# LCDTFT_FPC40P_DBI16B_3_2INCH_RTP.net
KiCad netlist of a schematic drawn in Altium Designer
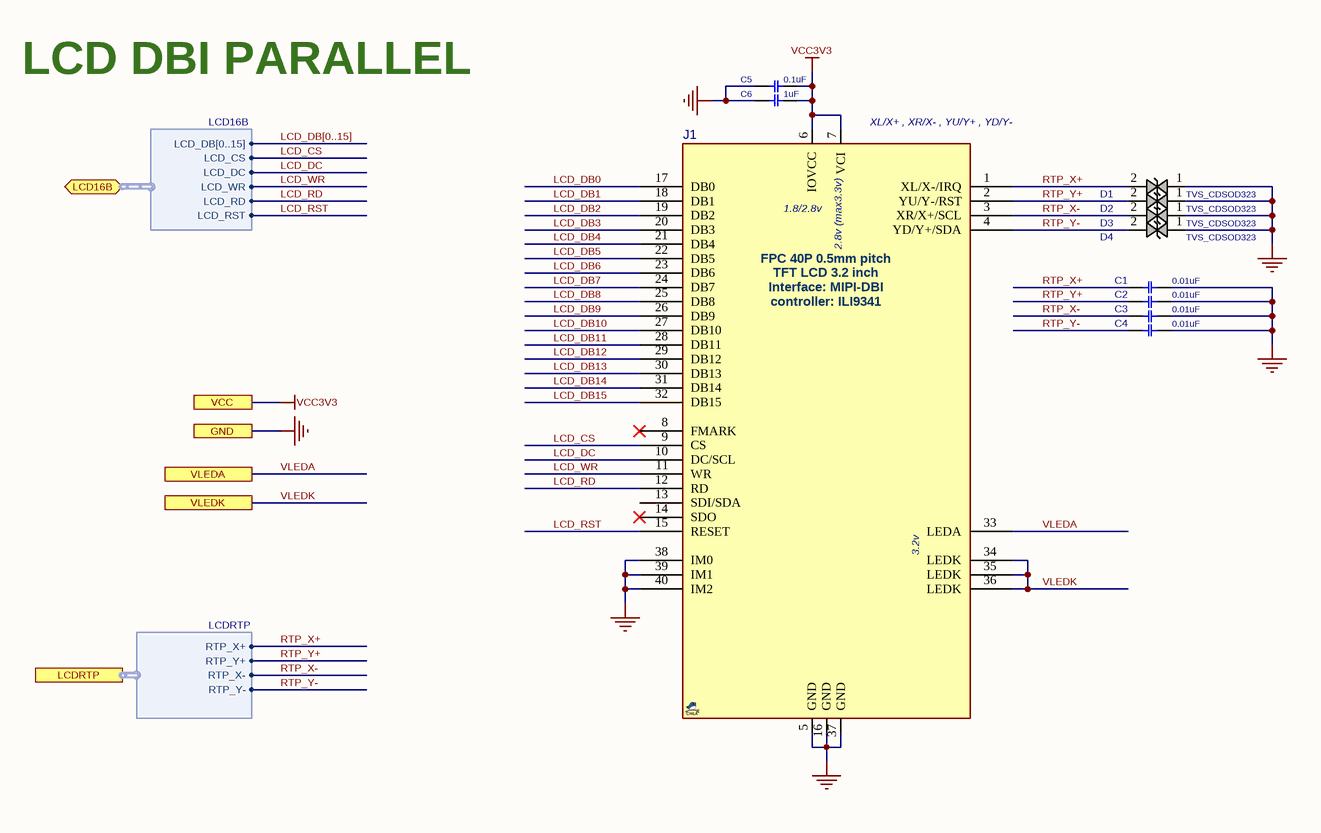
[diagram p0: LCDTFT_FPC40P_DBI16B_3.2INCH_RTP.SchDoc]

(export (version "E")
  (design (tool "Eeschema 10.0.6"))
  (components
    (comp (ref "C1")
      (value "0.01uF")
      (footprint "C0402")
      (description "CAP, MLCC")
      (libsource (lib "passive_smd") (part "CAP_SMD_MLCC"))
    )
    (comp (ref "C2")
      (value "0.01uF")
      (footprint "C0402")
      (description "CAP, MLCC")
      (libsource (lib "passive_smd") (part "CAP_SMD_MLCC"))
    )
    (comp (ref "C3")
      (value "0.01uF")
      (footprint "C0402")
      (description "CAP, MLCC")
      (libsource (lib "passive_smd") (part "CAP_SMD_MLCC"))
    )
    (comp (ref "C4")
      (value "0.01uF")
      (footprint "C0402")
      (description "CAP, MLCC")
      (libsource (lib "passive_smd") (part "CAP_SMD_MLCC"))
    )
    (comp (ref "C5")
      (value "0.1uF")
      (footprint "C0402")
      (description "CAP, MLCC")
      (fields (field (name "MANF_P#") "GRM155R71H104KE14D") (field (name "MANF") "Murata"))
      (libsource (lib "passive_smd") (part "CAP_SMD_MLCC"))
    )
    (comp (ref "C6")
      (value "1uF")
      (footprint "C0402")
      (description "CAP, MLCC")
      (libsource (lib "passive_smd") (part "CAP_SMD_MLCC"))
    )
    (comp (ref "D1")
      (value "TVS_CDSOD323")
      (footprint "D0805")
      (description "TVS, ESD PROTECT, Bidirectional")
      (fields (field (name "MANF_P#") "CDSOD323-T12C") (field (name "MANF") "Bourns"))
      (libsource (lib "protect_tvs_esd_fuse") (part "TVS_CDSOD323"))
    )
    (comp (ref "D2")
      (value "TVS_CDSOD323")
      (footprint "D0805")
      (description "TVS, ESD PROTECT, Bidirectional")
      (fields (field (name "MANF_P#") "CDSOD323-T12C") (field (name "MANF") "Bourns"))
      (libsource (lib "protect_tvs_esd_fuse") (part "TVS_CDSOD323"))
    )
    (comp (ref "D3")
      (value "TVS_CDSOD323")
      (footprint "D0805")
      (description "TVS, ESD PROTECT, Bidirectional")
      (fields (field (name "MANF_P#") "CDSOD323-T12C") (field (name "MANF") "Bourns"))
      (libsource (lib "protect_tvs_esd_fuse") (part "TVS_CDSOD323"))
    )
    (comp (ref "D4")
      (value "TVS_CDSOD323")
      (footprint "D0805")
      (description "TVS, ESD PROTECT, Bidirectional")
      (fields (field (name "MANF_P#") "CDSOD323-T12C") (field (name "MANF") "Bourns"))
      (libsource (lib "protect_tvs_esd_fuse") (part "TVS_CDSOD323"))
    )
    (comp (ref "J1")
      (value "FPC50_40")
      (footprint "FPC50_40T")
      (description "LCD TFT Color, FPC40P, 3.2\" with touch")
      (fields (field (name "MANF") "Hirose") (field (name "MANF_P#") "FH12A-40S-0.5SH"))
      (libsource (lib "lcdtft") (part "LCDTFT_DBI_FPC40P_3.2INCH"))
    )
  )
  (nets
    (net (code "3") (name "/LCD_CS") (class "Default")
      (node (ref "J1") (pin "9") (pinfunction "CS_9") (pintype "passive"))
    )
    (net (code "4") (name "/LCD_DB0") (class "Default")
      (node (ref "J1") (pin "17") (pinfunction "DB0_17") (pintype "passive"))
    )
    (net (code "5") (name "/LCD_DB1") (class "Default")
      (node (ref "J1") (pin "18") (pinfunction "DB1_18") (pintype "passive"))
    )
    (net (code "6") (name "/LCD_DB2") (class "Default")
      (node (ref "J1") (pin "19") (pinfunction "DB2_19") (pintype "passive"))
    )
    (net (code "7") (name "/LCD_DB3") (class "Default")
      (node (ref "J1") (pin "20") (pinfunction "DB3_20") (pintype "passive"))
    )
    (net (code "8") (name "/LCD_DB4") (class "Default")
      (node (ref "J1") (pin "21") (pinfunction "DB4_21") (pintype "passive"))
    )
    (net (code "9") (name "/LCD_DB5") (class "Default")
      (node (ref "J1") (pin "22") (pinfunction "DB5_22") (pintype "passive"))
    )
    (net (code "10") (name "/LCD_DB6") (class "Default")
      (node (ref "J1") (pin "23") (pinfunction "DB6_23") (pintype "passive"))
    )
    (net (code "11") (name "/LCD_DB7") (class "Default")
      (node (ref "J1") (pin "24") (pinfunction "DB7_24") (pintype "passive"))
    )
    (net (code "12") (name "/LCD_DB8") (class "Default")
      (node (ref "J1") (pin "25") (pinfunction "DB8_25") (pintype "passive"))
    )
    (net (code "13") (name "/LCD_DB9") (class "Default")
      (node (ref "J1") (pin "26") (pinfunction "DB9_26") (pintype "passive"))
    )
    (net (code "14") (name "/LCD_DB10") (class "Default")
      (node (ref "J1") (pin "27") (pinfunction "DB10_27") (pintype "passive"))
    )
    (net (code "15") (name "/LCD_DB11") (class "Default")
      (node (ref "J1") (pin "28") (pinfunction "DB11_28") (pintype "passive"))
    )
    (net (code "16") (name "/LCD_DB12") (class "Default")
      (node (ref "J1") (pin "29") (pinfunction "DB12_29") (pintype "passive"))
    )
    (net (code "17") (name "/LCD_DB13") (class "Default")
      (node (ref "J1") (pin "30") (pinfunction "DB13_30") (pintype "passive"))
    )
    (net (code "18") (name "/LCD_DB14") (class "Default")
      (node (ref "J1") (pin "31") (pinfunction "DB14_31") (pintype "passive"))
    )
    (net (code "19") (name "/LCD_DB15") (class "Default")
      (node (ref "J1") (pin "32") (pinfunction "DB15_32") (pintype "passive"))
    )
    (net (code "21") (name "/LCD_DC") (class "Default")
      (node (ref "J1") (pin "10") (pinfunction "DC/SCL_10") (pintype "passive"))
    )
    (net (code "22") (name "/LCD_RD") (class "Default")
      (node (ref "J1") (pin "12") (pinfunction "RD_12") (pintype "passive"))
    )
    (net (code "23") (name "/LCD_RST") (class "Default")
      (node (ref "J1") (pin "15") (pinfunction "RESET_15") (pintype "passive"))
    )
    (net (code "24") (name "/LCD_WR") (class "Default")
      (node (ref "J1") (pin "11") (pinfunction "WR_11") (pintype "passive"))
    )
    (net (code "25") (name "/RTP_X+") (class "Default")
      (node (ref "C1") (pin "2") (pinfunction "2_2") (pintype "passive"))
      (node (ref "D1") (pin "2") (pinfunction "2_2") (pintype "passive"))
      (node (ref "J1") (pin "1") (pinfunction "XL/X-/IRQ_1") (pintype "passive"))
    )
    (net (code "26") (name "/RTP_X-") (class "Default")
      (node (ref "C3") (pin "2") (pinfunction "2_2") (pintype "passive"))
      (node (ref "D3") (pin "2") (pinfunction "2_2") (pintype "passive"))
      (node (ref "J1") (pin "3") (pinfunction "XR/X+/SCL_3") (pintype "passive"))
    )
    (net (code "27") (name "/RTP_Y+") (class "Default")
      (node (ref "C2") (pin "2") (pinfunction "2_2") (pintype "passive"))
      (node (ref "D2") (pin "2") (pinfunction "2_2") (pintype "passive"))
      (node (ref "J1") (pin "2") (pinfunction "YU/Y-/RST_2") (pintype "passive"))
    )
    (net (code "28") (name "/RTP_Y-") (class "Default")
      (node (ref "C4") (pin "2") (pinfunction "2_2") (pintype "passive"))
      (node (ref "D4") (pin "2") (pinfunction "2_2") (pintype "passive"))
      (node (ref "J1") (pin "4") (pinfunction "YD/Y+/SDA_4") (pintype "passive"))
    )
    (net (code "29") (name "/VLEDA") (class "Default")
      (node (ref "J1") (pin "33") (pinfunction "LEDA_33") (pintype "passive"))
    )
    (net (code "30") (name "/VLEDK") (class "Default")
      (node (ref "J1") (pin "34") (pinfunction "LEDK_34") (pintype "passive"))
      (node (ref "J1") (pin "35") (pinfunction "LEDK_35") (pintype "passive"))
      (node (ref "J1") (pin "36") (pinfunction "LEDK_36") (pintype "passive"))
    )
    (net (code "33") (name "GND") (class "Default")
      (node (ref "C1") (pin "1") (pinfunction "1_1") (pintype "passive"))
      (node (ref "C2") (pin "1") (pinfunction "1_1") (pintype "passive"))
      (node (ref "C3") (pin "1") (pinfunction "1_1") (pintype "passive"))
      (node (ref "C4") (pin "1") (pinfunction "1_1") (pintype "passive"))
      (node (ref "C5") (pin "2") (pinfunction "2_2") (pintype "passive"))
      (node (ref "C6") (pin "2") (pinfunction "2_2") (pintype "passive"))
      (node (ref "D1") (pin "1") (pinfunction "1_1") (pintype "passive"))
      (node (ref "D2") (pin "1") (pinfunction "1_1") (pintype "passive"))
      (node (ref "D3") (pin "1") (pinfunction "1_1") (pintype "passive"))
      (node (ref "D4") (pin "1") (pinfunction "1_1") (pintype "passive"))
      (node (ref "J1") (pin "16") (pinfunction "GND_16") (pintype "passive"))
      (node (ref "J1") (pin "37") (pinfunction "GND_37") (pintype "passive"))
      (node (ref "J1") (pin "38") (pinfunction "IM0_38") (pintype "passive"))
      (node (ref "J1") (pin "39") (pinfunction "IM1_39") (pintype "passive"))
      (node (ref "J1") (pin "40") (pinfunction "IM2_40") (pintype "passive"))
      (node (ref "J1") (pin "5") (pinfunction "GND_5") (pintype "passive"))
    )
    (net (code "34") (name "VCC3V3") (class "Default")
      (node (ref "C5") (pin "1") (pinfunction "1_1") (pintype "passive"))
      (node (ref "C6") (pin "1") (pinfunction "1_1") (pintype "passive"))
      (node (ref "J1") (pin "6") (pinfunction "IOVCC_6") (pintype "passive"))
      (node (ref "J1") (pin "7") (pinfunction "VCI_7") (pintype "passive"))
    )
    (net (code "35") (name "unconnected-(J1-FMARK-Pad8)") (class "Default")
      (node (ref "J1") (pin "8") (pinfunction "FMARK_8") (pintype "passive+no_connect"))
    )
    (net (code "36") (name "unconnected-(J1-SDI{slash}SDA-Pad13)") (class "Default")
      (node (ref "J1") (pin "13") (pinfunction "SDI/SDA_13") (pintype "passive"))
    )
    (net (code "37") (name "unconnected-(J1-SDO-Pad14)") (class "Default")
      (node (ref "J1") (pin "14") (pinfunction "SDO_14") (pintype "passive+no_connect"))
    )
  )
)
